# main.net
KiCad netlist of a schematic drawn in Altium Designer
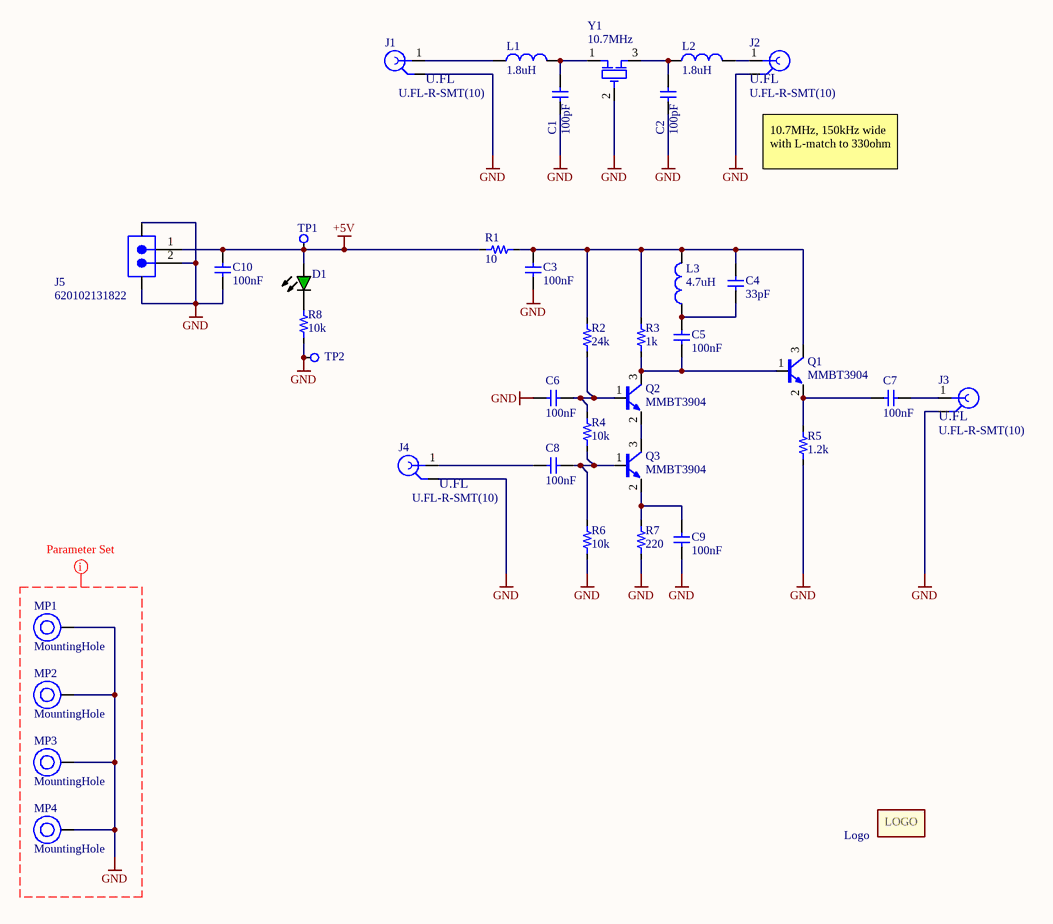
[diagram p0: main.SchDoc]

(export (version "E")
  (design (tool "Eeschema 10.0.6"))
  (components
    (comp (ref "C1")
      (value "100pF")
      (footprint "0603-C-N")
      (description "WCAP-CSGP Multilayer Ceramic Chip Capacitor, General Purpose, size 0603, NP0, 100pF, 50VDC")
      (fields (field (name "TOLERANCE") "5%") (field (name "PAGE PART #") "CCQJ101"))
      (libsource (lib "7c7 Engineering") (part "CAP-NP-2"))
    )
    (comp (ref "C2")
      (value "100pF")
      (footprint "0603-C-N")
      (description "WCAP-CSGP Multilayer Ceramic Chip Capacitor, General Purpose, size 0603, NP0, 100pF, 50VDC")
      (fields (field (name "TOLERANCE") "5%") (field (name "PAGE PART #") "CCQJ101"))
      (libsource (lib "7c7 Engineering") (part "CAP-NP-2"))
    )
    (comp (ref "C3")
      (value "100nF")
      (footprint "0603-C-N")
      (description "Capacitor MLCC, General Purpose, size 0603, X7R, 100nF, +/-10%, 50V")
      (fields (field (name "JLCPCB PART #") "C14663") (field (name "TOLERANCE") "10%"))
      (libsource (lib "7c7 Engineering") (part "CAP-NP-2"))
    )
    (comp (ref "C4")
      (value "33pF")
      (footprint "0603-C-N")
      (description "WCAP-CSGP Multilayer Ceramic Chip Capacitor, General Purpose, size 0603, NP0, 33pF, 50VDC")
      (fields (field (name "TOLERANCE") "5%") (field (name "JLCPCB BASIC PART") "Yes"))
      (libsource (lib "7c7 Engineering") (part "CAP-NP-2"))
    )
    (comp (ref "C5")
      (value "100nF")
      (footprint "0603-C-N")
      (description "Capacitor MLCC, General Purpose, size 0603, X7R, 100nF, +/-10%, 50V")
      (fields (field (name "JLCPCB PART #") "C14663") (field (name "TOLERANCE") "10%"))
      (libsource (lib "7c7 Engineering") (part "CAP-NP-2"))
    )
    (comp (ref "C6")
      (value "100nF")
      (footprint "0603-C-N")
      (description "Capacitor MLCC, General Purpose, size 0603, X7R, 100nF, +/-10%, 50V")
      (fields (field (name "JLCPCB PART #") "C14663") (field (name "TOLERANCE") "10%"))
      (libsource (lib "7c7 Engineering") (part "CAP-NP-2"))
    )
    (comp (ref "C7")
      (value "100nF")
      (footprint "0603-C-N")
      (description "Capacitor MLCC, General Purpose, size 0603, X7R, 100nF, +/-10%, 50V")
      (fields (field (name "JLCPCB PART #") "C14663") (field (name "TOLERANCE") "10%"))
      (libsource (lib "7c7 Engineering") (part "CAP-NP-2"))
    )
    (comp (ref "C8")
      (value "100nF")
      (footprint "0603-C-N")
      (description "Capacitor MLCC, General Purpose, size 0603, X7R, 100nF, +/-10%, 50V")
      (fields (field (name "JLCPCB PART #") "C14663") (field (name "TOLERANCE") "10%"))
      (libsource (lib "7c7 Engineering") (part "CAP-NP-2"))
    )
    (comp (ref "C9")
      (value "100nF")
      (footprint "0603-C-N")
      (description "Capacitor MLCC, General Purpose, size 0603, X7R, 100nF, +/-10%, 50V")
      (fields (field (name "JLCPCB PART #") "C14663") (field (name "TOLERANCE") "10%"))
      (libsource (lib "7c7 Engineering") (part "CAP-NP-2"))
    )
    (comp (ref "C10")
      (value "100nF")
      (footprint "0603-C-N")
      (description "Capacitor MLCC, General Purpose, size 0603, X7R, 100nF, +/-10%, 50V")
      (fields (field (name "TOLERANCE") "10%") (field (name "PAGE PART #") "CCQK104"))
      (libsource (lib "7c7 Engineering") (part "CAP-NP-2"))
    )
    (comp (ref "D1")
      (value "150060GS84000")
      (footprint "WL-SMCW_0603_150060xx8x000")
      (description "WL-SMCW Mono-color Chip LED Waterclear, size 0603, Green, 3.3V, 40°")
      (fields (field (name "JLCPCB PART #") "C7429914") (field (name "MANUFACTURER") "Wurth Elektronik"))
      (libsource (lib "7c7 Engineering") (part "LED-GREEN-2"))
    )
    (comp (ref "GR1")
      (value "Logo")
      (footprint "LOGO_9x6mm")
      (libsource (lib "Integrated_Library_LieBtrau") (part "Logo"))
    )
    (comp (ref "J1")
      (value "U.FL-R-SMT(10)")
      (footprint "HRS-U.FL-R-SMT_V")
      (fields (field (name "JLCPCB PART #") "C88373") (field (name "MANUFACTURER") "Hirose Electric"))
      (libsource (lib "") (part "CN_COAX_1"))
    )
    (comp (ref "J2")
      (value "U.FL-R-SMT(10)")
      (footprint "HRS-U.FL-R-SMT_V")
      (fields (field (name "JLCPCB PART #") "C88373") (field (name "MANUFACTURER") "Hirose Electric"))
      (libsource (lib "7c7 Engineering") (part "CN_COAX"))
    )
    (comp (ref "J3")
      (value "U.FL-R-SMT(10)")
      (footprint "HRS-U.FL-R-SMT_V")
      (fields (field (name "JLCPCB PART #") "C88373") (field (name "MANUFACTURER") "Hirose Electric"))
      (libsource (lib "7c7 Engineering") (part "CN_COAX"))
    )
    (comp (ref "J4")
      (value "U.FL-R-SMT(10)")
      (footprint "HRS-U.FL-R-SMT_V")
      (fields (field (name "JLCPCB PART #") "C88373") (field (name "MANUFACTURER") "Hirose Electric"))
      (libsource (lib "") (part "CN_COAX_1"))
    )
    (comp (ref "J5")
      (value "620102131822")
      (footprint "620102131822")
      (description "WR-WTB SMT Male Horizontal Shrouded Header, pitch 2mm, 2p")
      (fields
        (field (name "JLCPCB PART #") "C295747")
        (field (name "PAGE PART #") "K620102131822")
        (field (name "PUBLISHER") "Wurth Elektronik")
      )
      (libsource (lib "7c7 Engineering") (part "HDR_2P_2MP"))
    )
    (comp (ref "L1")
      (value "1.8uH")
      (footprint "WE-KI_1008")
      (description "Ind Chip Unshielded Wirewound 1.8uH 2% 7.9MHz 39Q-Factor Ferrite 600mA 1008 T/R")
      (fields (field (name "TOLERANCE") "2%") (field (name "JLCPCB BASIC PART") "No"))
      (libsource (lib "7c7 Engineering") (part "IND"))
    )
    (comp (ref "L2")
      (value "1.8uH")
      (footprint "WE-KI_1008")
      (description "Ind Chip Unshielded Wirewound 1.8uH 2% 7.9MHz 39Q-Factor Ferrite 600mA 1008 T/R")
      (fields (field (name "TOLERANCE") "2%") (field (name "JLCPCB BASIC PART") "No"))
      (libsource (lib "7c7 Engineering") (part "IND"))
    )
    (comp (ref "L3")
      (value "4.7uH")
      (footprint "WE-KI_1008")
      (description "Inductor RF Wirewound 4.7uH 2% 7.9MHz 31Q-Factor Ferrite 0.4A 1.68Ohm DCR 1008 T/R")
      (fields (field (name "TOLERANCE") "2%") (field (name "JLCPCB BASIC PART") "No"))
      (libsource (lib "7c7 Engineering") (part "IND"))
    )
    (comp (ref "MP1")
      (value "MountingHole")
      (footprint "PTH-M3D6.5_VIA-RING")
      (libsource (lib "7c7 Engineering") (part "MECH_NO_BOM"))
    )
    (comp (ref "MP2")
      (value "MountingHole")
      (footprint "PTH-M3D6.5_VIA-RING")
      (libsource (lib "7c7 Engineering") (part "MECH_NO_BOM"))
    )
    (comp (ref "MP3")
      (value "MountingHole")
      (footprint "PTH-M3D6.5_VIA-RING")
      (libsource (lib "7c7 Engineering") (part "MECH_NO_BOM"))
    )
    (comp (ref "MP4")
      (value "MountingHole")
      (footprint "PTH-M3D6.5_VIA-RING")
      (libsource (lib "7c7 Engineering") (part "MECH_NO_BOM"))
    )
    (comp (ref "Q1")
      (value "MMBT3904")
      (footprint "SOT-23-3-N")
      (description "NPN General Purpose Amplifier, 40 V, 0.2 A, -55 to 150 degC, 3-Pin SOT23, RoHS, Tape and Reel")
      (fields (field (name "MANUFACTURER") "Fairchild Semiconductor") (field (name "POWER") "625mW"))
      (libsource (lib "7c7 Engineering") (part "BJT-NPN-BEC"))
    )
    (comp (ref "Q2")
      (value "MMBT3904")
      (footprint "SOT-23-3-N")
      (description "NPN General Purpose Amplifier, 40 V, 0.2 A, -55 to 150 degC, 3-Pin SOT23, RoHS, Tape and Reel")
      (fields (field (name "MANUFACTURER") "Fairchild Semiconductor") (field (name "POWER") "625mW"))
      (libsource (lib "7c7 Engineering") (part "BJT-NPN-BEC"))
    )
    (comp (ref "Q3")
      (value "MMBT3904")
      (footprint "SOT-23-3-N")
      (description "NPN General Purpose Amplifier, 40 V, 0.2 A, -55 to 150 degC, 3-Pin SOT23, RoHS, Tape and Reel")
      (fields (field (name "MANUFACTURER") "Fairchild Semiconductor") (field (name "POWER") "625mW"))
      (libsource (lib "7c7 Engineering") (part "BJT-NPN-BEC"))
    )
    (comp (ref "R1")
      (value "10")
      (footprint "0603-R-N")
      (description "Chip Resistor, Thick Film, General Purpose, 0603, 100mW, 50V, 10 Ohm, +/-1%")
      (fields (field (name "TOLERANCE") "1%") (field (name "JLCPCB PART #") "C22859"))
      (libsource (lib "7c7 Engineering") (part "RES"))
    )
    (comp (ref "R2")
      (value "24k")
      (footprint "0603-R-N")
      (description "Chip Resistor, Thick Film, General Purpose, 0603, 100mW, 50V, 24 kOhm, +/-1%")
      (fields (field (name "TOLERANCE") "1%") (field (name "JLCPCB BASIC PART") "Yes"))
      (libsource (lib "7c7 Engineering") (part "RES"))
    )
    (comp (ref "R3")
      (value "1k")
      (footprint "0603-R-N")
      (description "Chip Resistor, Thick Film, General Purpose, 0603, 100mW, 50V, 1 kOhm, +/-1%")
      (fields (field (name "JLCPCB PART #") "C21190") (field (name "TOLERANCE") "1%"))
      (libsource (lib "7c7 Engineering") (part "RES"))
    )
    (comp (ref "R4")
      (value "10k")
      (footprint "0603-R-N")
      (description "Chip Resistor, Thick Film, General Purpose, 0603, 100mW, 50V, 10 kOhm, +/-1%")
      (fields (field (name "FLIR PART #") "YRES10K-1") (field (name "PAGE PART #") "ROQF1002"))
      (libsource (lib "7c7 Engineering") (part "RES"))
    )
    (comp (ref "R5")
      (value "1.2k")
      (footprint "0603-R-N")
      (description "Chip Resistor, Thick Film, General Purpose, 0603, 100mW, 50V, 1.2 kOhm, +/-1%")
      (fields (field (name "TOLERANCE") "1%") (field (name "JLCPCB PART #") "C22765"))
      (libsource (lib "7c7 Engineering") (part "RES"))
    )
    (comp (ref "R6")
      (value "10k")
      (footprint "0603-R-N")
      (description "Chip Resistor, Thick Film, General Purpose, 0603, 100mW, 50V, 10 kOhm, +/-1%")
      (fields (field (name "FLIR PART #") "YRES10K-1") (field (name "PAGE PART #") "ROQF1002"))
      (libsource (lib "7c7 Engineering") (part "RES"))
    )
    (comp (ref "R7")
      (value "220")
      (footprint "0603-R-N")
      (description "Res Thick Film 0603 220 Ohm 1% 0.1W(1/10W) ±100ppm/C Pad SMD T/R Automotive AEC-Q200")
      (fields (field (name "TOLERANCE") "1%") (field (name "JLCPCB PART #") "C22962"))
      (libsource (lib "7c7 Engineering") (part "RES"))
    )
    (comp (ref "R8")
      (value "10k")
      (footprint "0603-R-N")
      (description "Chip Resistor, Thick Film, General Purpose, 0603, 100mW, 50V, 10 kOhm, +/-1%")
      (fields (field (name "FLIR PART #") "YRES10K-1") (field (name "PAGE PART #") "ROQF1002"))
      (libsource (lib "7c7 Engineering") (part "RES"))
    )
    (comp (ref "TP1")
      (value "Testpad with multiple sizes")
      (footprint "TP_1.5mm_0.3mmHole")
      (description "Testpad land")
      (libsource (lib "7c7 Engineering") (part "Testpad"))
    )
    (comp (ref "TP2")
      (value "Testpad with multiple sizes")
      (footprint "TP_1.5mm_0.3mmHole")
      (description "Testpad land")
      (libsource (lib "7c7 Engineering") (part "Testpad"))
    )
    (comp (ref "Y1")
      (value "SFECV10M7JA00-R0")
      (footprint "FP-SFECV10M7JA00-R0-MFG")
      (description "SFECV Series 10.7 MHz 2 Element 150 kHz Bw 330 Ohm Surface Mount Ceramic Filter")
      (fields (field (name "FREQUENCY") "10.7MHz"))
      (libsource (lib "7c7 Engineering") (part "XTAL-3"))
    )
  )
  (nets
    (net (code "1") (name "+5V") (class "Default")
      (node (ref "C10") (pin "2") (pinfunction "2_2") (pintype "passive"))
      (node (ref "D1") (pin "2") (pinfunction "A_2") (pintype "passive"))
      (node (ref "J5") (pin "1") (pinfunction "1_1") (pintype "passive"))
      (node (ref "R1") (pin "2") (pinfunction "2_2") (pintype "passive"))
      (node (ref "TP1") (pin "1") (pinfunction "Pad_1") (pintype "passive"))
    )
    (net (code "2") (name "GND") (class "Default")
      (node (ref "C1") (pin "1") (pinfunction "1_1") (pintype "passive"))
      (node (ref "C10") (pin "1") (pinfunction "1_1") (pintype "passive"))
      (node (ref "C2") (pin "1") (pinfunction "1_1") (pintype "passive"))
      (node (ref "C3") (pin "1") (pinfunction "1_1") (pintype "passive"))
      (node (ref "C6") (pin "2") (pinfunction "2_2") (pintype "passive"))
      (node (ref "C9") (pin "1") (pinfunction "1_1") (pintype "passive"))
      (node (ref "J1") (pin "2") (pinfunction "GND_2") (pintype "passive"))
      (node (ref "J2") (pin "2") (pinfunction "GND_2") (pintype "passive"))
      (node (ref "J3") (pin "2") (pinfunction "GND_2") (pintype "passive"))
      (node (ref "J4") (pin "2") (pinfunction "GND_2") (pintype "passive"))
      (node (ref "J5") (pin "2") (pinfunction "2_2") (pintype "passive"))
      (node (ref "J5") (pin "MP1") (pinfunction "MP1_MP1") (pintype "passive"))
      (node (ref "J5") (pin "MP2") (pinfunction "MP2_MP2") (pintype "passive"))
      (node (ref "MP1") (pin "1") (pinfunction "H1_1") (pintype "passive"))
      (node (ref "MP2") (pin "1") (pinfunction "H1_1") (pintype "passive"))
      (node (ref "MP3") (pin "1") (pinfunction "H1_1") (pintype "passive"))
      (node (ref "MP4") (pin "1") (pinfunction "H1_1") (pintype "passive"))
      (node (ref "R5") (pin "1") (pinfunction "1_1") (pintype "passive"))
      (node (ref "R6") (pin "1") (pinfunction "1_1") (pintype "passive"))
      (node (ref "R7") (pin "1") (pinfunction "1_1") (pintype "passive"))
      (node (ref "R8") (pin "1") (pinfunction "1_1") (pintype "passive"))
      (node (ref "TP2") (pin "1") (pinfunction "Pad_1") (pintype "passive"))
      (node (ref "Y1") (pin "2") (pinfunction "2_2") (pintype "passive"))
    )
    (net (code "3") (name "Net-(C1-Pad2)") (class "Default")
      (node (ref "C1") (pin "2") (pinfunction "2_2") (pintype "passive"))
      (node (ref "L1") (pin "2") (pinfunction "2_2") (pintype "passive"))
      (node (ref "Y1") (pin "1") (pinfunction "1_1") (pintype "passive"))
    )
    (net (code "4") (name "Net-(C2-Pad2)") (class "Default")
      (node (ref "C2") (pin "2") (pinfunction "2_2") (pintype "passive"))
      (node (ref "L2") (pin "1") (pinfunction "1_1") (pintype "passive"))
      (node (ref "Y1") (pin "3") (pinfunction "3_3") (pintype "passive"))
    )
    (net (code "5") (name "Net-(C4-Pad1)") (class "Default")
      (node (ref "C4") (pin "1") (pinfunction "1_1") (pintype "passive"))
      (node (ref "C5") (pin "1") (pinfunction "1_1") (pintype "passive"))
      (node (ref "L3") (pin "1") (pinfunction "1_1") (pintype "passive"))
    )
    (net (code "6") (name "Net-(D1-K)") (class "Default")
      (node (ref "D1") (pin "1") (pinfunction "K_1") (pintype "passive"))
      (node (ref "R8") (pin "2") (pinfunction "2_2") (pintype "passive"))
    )
    (net (code "7") (name "Net-(J1-SIG)") (class "Default")
      (node (ref "J1") (pin "1") (pinfunction "SIG_1") (pintype "passive"))
      (node (ref "L1") (pin "1") (pinfunction "1_1") (pintype "passive"))
    )
    (net (code "8") (name "Net-(J2-SIG)") (class "Default")
      (node (ref "J2") (pin "1") (pinfunction "SIG_1") (pintype "passive"))
      (node (ref "L2") (pin "2") (pinfunction "2_2") (pintype "passive"))
    )
    (net (code "9") (name "Net-(J3-SIG)") (class "Default")
      (node (ref "C7") (pin "1") (pinfunction "1_1") (pintype "passive"))
      (node (ref "J3") (pin "1") (pinfunction "SIG_1") (pintype "passive"))
    )
    (net (code "10") (name "Net-(J4-SIG)") (class "Default")
      (node (ref "C8") (pin "2") (pinfunction "2_2") (pintype "passive"))
      (node (ref "J4") (pin "1") (pinfunction "SIG_1") (pintype "passive"))
    )
    (net (code "11") (name "Net-(Q1-B)") (class "Default")
      (node (ref "C5") (pin "2") (pinfunction "2_2") (pintype "passive"))
      (node (ref "Q1") (pin "1") (pinfunction "B_1") (pintype "passive"))
      (node (ref "Q2") (pin "3") (pinfunction "C_3") (pintype "passive"))
      (node (ref "R3") (pin "1") (pinfunction "1_1") (pintype "passive"))
    )
    (net (code "12") (name "Net-(Q1-C)") (class "Default")
      (node (ref "C3") (pin "2") (pinfunction "2_2") (pintype "passive"))
      (node (ref "C4") (pin "2") (pinfunction "2_2") (pintype "passive"))
      (node (ref "L3") (pin "2") (pinfunction "2_2") (pintype "passive"))
      (node (ref "Q1") (pin "3") (pinfunction "C_3") (pintype "passive"))
      (node (ref "R1") (pin "1") (pinfunction "1_1") (pintype "passive"))
      (node (ref "R2") (pin "2") (pinfunction "2_2") (pintype "passive"))
      (node (ref "R3") (pin "2") (pinfunction "2_2") (pintype "passive"))
    )
    (net (code "13") (name "Net-(Q1-E)") (class "Default")
      (node (ref "C7") (pin "2") (pinfunction "2_2") (pintype "passive"))
      (node (ref "Q1") (pin "2") (pinfunction "E_2") (pintype "passive"))
      (node (ref "R5") (pin "2") (pinfunction "2_2") (pintype "passive"))
    )
    (net (code "14") (name "Net-(Q2-B)") (class "Default")
      (node (ref "C6") (pin "1") (pinfunction "1_1") (pintype "passive"))
      (node (ref "Q2") (pin "1") (pinfunction "B_1") (pintype "passive"))
      (node (ref "R2") (pin "1") (pinfunction "1_1") (pintype "passive"))
      (node (ref "R4") (pin "2") (pinfunction "2_2") (pintype "passive"))
    )
    (net (code "15") (name "Net-(Q2-E)") (class "Default")
      (node (ref "Q2") (pin "2") (pinfunction "E_2") (pintype "passive"))
      (node (ref "Q3") (pin "3") (pinfunction "C_3") (pintype "passive"))
    )
    (net (code "16") (name "Net-(Q3-B)") (class "Default")
      (node (ref "C8") (pin "1") (pinfunction "1_1") (pintype "passive"))
      (node (ref "Q3") (pin "1") (pinfunction "B_1") (pintype "passive"))
      (node (ref "R4") (pin "1") (pinfunction "1_1") (pintype "passive"))
      (node (ref "R6") (pin "2") (pinfunction "2_2") (pintype "passive"))
    )
    (net (code "17") (name "Net-(Q3-E)") (class "Default")
      (node (ref "C9") (pin "2") (pinfunction "2_2") (pintype "passive"))
      (node (ref "Q3") (pin "2") (pinfunction "E_2") (pintype "passive"))
      (node (ref "R7") (pin "2") (pinfunction "2_2") (pintype "passive"))
    )
  )
)
